# Light.net
KiCad netlist of a schematic drawn in EAGLE
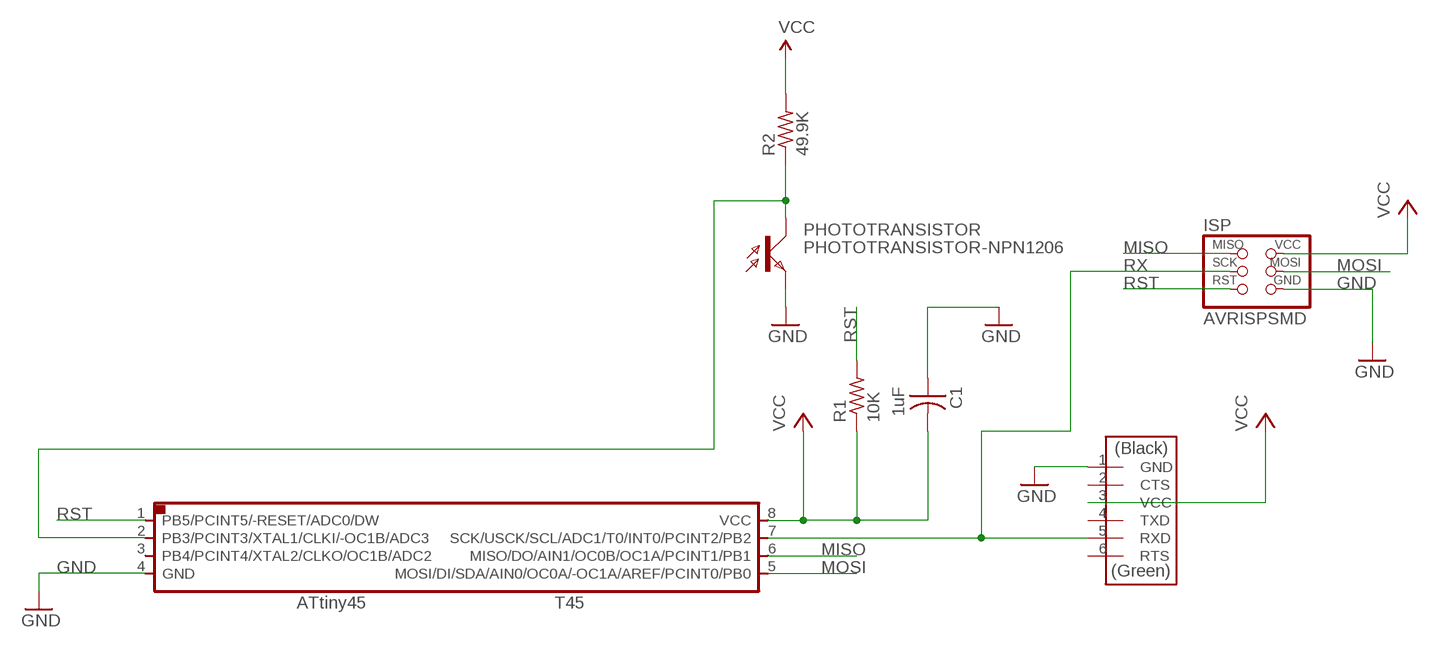
[diagram p0: schematic, sheet 1]

(export (version "E")
  (design (tool "Eeschema 10.0.6"))
  (components
    (comp (ref "C1")
      (value "1uF")
      (footprint "eagle-import:C1206FAB")
      (libsource (lib "eagle-import") (part "CAP-US1206FAB"))
    )
    (comp (ref "FDTI")
      (value "FTDI-SMD-HEADER")
      (footprint "eagle-import:1X06SMD")
      (libsource (lib "eagle-import") (part "FTDI-SMD-HEADER"))
    )
    (comp (ref "ISP")
      (value "AVRISPSMD")
      (footprint "eagle-import:2X03SMD")
      (libsource (lib "eagle-import") (part "AVRISPSMD"))
    )
    (comp (ref "PHOTOTRANSISTOR")
      (value "PHOTOTRANSISTOR-NPN1206")
      (footprint "eagle-import:OP1206")
      (libsource (lib "eagle-import") (part "PHOTOTRANSISTOR-NPN1206"))
    )
    (comp (ref "R1")
      (value "10K")
      (footprint "eagle-import:R1206FAB")
      (libsource (lib "eagle-import") (part "RES-US1206FAB"))
    )
    (comp (ref "R2")
      (value "49.9K")
      (footprint "eagle-import:R1206FAB")
      (libsource (lib "eagle-import") (part "RES-US1206FAB"))
    )
    (comp (ref "T45")
      (value "ATTINY45SI")
      (footprint "eagle-import:SOIC8")
      (libsource (lib "eagle-import") (part "ATTINY45SI"))
    )
  )
  (nets
    (net (code "1") (name "/MISO") (class "Default")
      (node (ref "ISP") (pin "1") (pinfunction "MISO_1") (pintype "passive"))
      (node (ref "T45") (pin "6") (pinfunction "MISO/DO/AIN1/OC0B/OC1A/PCINT1/PB1_6") (pintype "bidirectional"))
    )
    (net (code "2") (name "/MOSI") (class "Default")
      (node (ref "ISP") (pin "4") (pinfunction "MOSI_4") (pintype "passive"))
      (node (ref "T45") (pin "5") (pinfunction "MOSI/DI/SDA/AIN0/OC0A/-OC1A/AREF/PCINT0/PB0_5") (pintype "bidirectional"))
    )
    (net (code "3") (name "/RST") (class "Default")
      (node (ref "ISP") (pin "5") (pinfunction "RST_5") (pintype "passive"))
      (node (ref "R1") (pin "2") (pinfunction "2_2") (pintype "passive"))
      (node (ref "T45") (pin "1") (pinfunction "PB5/PCINT5/-RESET/ADC0/DW_1") (pintype "bidirectional"))
    )
    (net (code "4") (name "/RX") (class "Default")
      (node (ref "FDTI") (pin "5") (pinfunction "RXD_5") (pintype "bidirectional"))
      (node (ref "ISP") (pin "3") (pinfunction "SCK_3") (pintype "passive"))
      (node (ref "T45") (pin "7") (pinfunction "SCK/USCK/SCL/ADC1/T0/INT0/PCINT2/PB2_7") (pintype "bidirectional"))
    )
    (net (code "5") (name "GND") (class "Default")
      (node (ref "C1") (pin "1") (pinfunction "1_1") (pintype "passive"))
      (node (ref "FDTI") (pin "1") (pinfunction "GND_1") (pintype "bidirectional"))
      (node (ref "ISP") (pin "6") (pinfunction "GND_6") (pintype "passive"))
      (node (ref "PHOTOTRANSISTOR") (pin "EMITTER") (pinfunction "E_EMITTER") (pintype "passive"))
      (node (ref "T45") (pin "4") (pinfunction "GND_4") (pintype "bidirectional"))
    )
    (net (code "6") (name "Net-(PHOTOTRANSISTOR-C)") (class "Default")
      (node (ref "PHOTOTRANSISTOR") (pin "COLLECTOR") (pinfunction "C_COLLECTOR") (pintype "passive"))
      (node (ref "R2") (pin "1") (pinfunction "1_1") (pintype "passive"))
      (node (ref "T45") (pin "2") (pinfunction "PB3/PCINT3/XTAL1/CLKI/-OC1B/ADC3_2") (pintype "bidirectional"))
    )
    (net (code "7") (name "VCC") (class "Default")
      (node (ref "C1") (pin "2") (pinfunction "2_2") (pintype "passive"))
      (node (ref "FDTI") (pin "3") (pinfunction "VCC_3") (pintype "bidirectional"))
      (node (ref "ISP") (pin "2") (pinfunction "VCC_2") (pintype "passive"))
      (node (ref "R1") (pin "1") (pinfunction "1_1") (pintype "passive"))
      (node (ref "R2") (pin "2") (pinfunction "2_2") (pintype "passive"))
      (node (ref "T45") (pin "8") (pinfunction "VCC_8") (pintype "bidirectional"))
    )
    (net (code "8") (name "unconnected-(FDTI-CTS-Pad2)") (class "Default")
      (node (ref "FDTI") (pin "2") (pinfunction "CTS_2") (pintype "bidirectional"))
    )
    (net (code "9") (name "unconnected-(FDTI-RTS-Pad6)") (class "Default")
      (node (ref "FDTI") (pin "6") (pinfunction "RTS_6") (pintype "bidirectional"))
    )
    (net (code "10") (name "unconnected-(FDTI-TXD-Pad4)") (class "Default")
      (node (ref "FDTI") (pin "4") (pinfunction "TXD_4") (pintype "bidirectional"))
    )
    (net (code "11") (name "unconnected-(T45-PB4{slash}PCINT4{slash}XTAL2{slash}CLKO{slash}OC1B{slash}ADC2-Pad3)") (class "Default")
      (node (ref "T45") (pin "3") (pinfunction "PB4/PCINT4/XTAL2/CLKO/OC1B/ADC2_3") (pintype "bidirectional"))
    )
  )
)
